# LM3488_Sheet1.net
KiCad netlist of a schematic drawn in Altium Designer
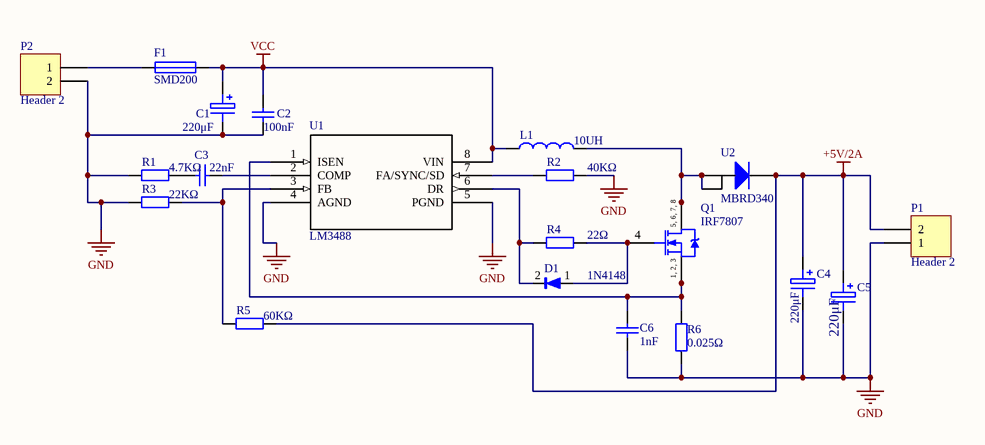
[diagram p0: LM3488_Sheet1.SchDoc]

(export (version "E")
  (design (tool "Eeschema 10.0.6"))
  (components
    (comp (ref "C1")
      (value "220μF")
      (footprint "RB-220T")
      (description "Electrolytic Capacitor")
      (libsource (lib "myIntegrated_Library1") (part "CAP ELECTRO1"))
    )
    (comp (ref "C2")
      (value "100nF")
      (footprint "0805")
      (description "Capacitor")
      (fields (field (name "Comment") "Cap") (field (name "PUBLISHER") "Altium Limited"))
      (libsource (lib "Miscellaneous Devices") (part "Cap"))
    )
    (comp (ref "C3")
      (value "22nF")
      (footprint "0805")
      (description "Capacitor")
      (fields (field (name "Comment") "Cap") (field (name "PUBLISHER") "Altium Limited"))
      (libsource (lib "Miscellaneous Devices") (part "Cap"))
    )
    (comp (ref "C4")
      (value "220μF,16V,Ф6.3×7.7mm")
      (footprint "RB-220T")
      (description "Electrolytic Capacitor")
      (fields (field (name "规格型号") "220μF"))
      (libsource (lib "myIntegrated_Library1") (part "CAP ELECTRO1"))
    )
    (comp (ref "C5")
      (value "220μF,16V,Ф6.3×7.7mm")
      (footprint "RB-220T")
      (description "Electrolytic Capacitor")
      (fields (field (name "规格型号") "220μF"))
      (libsource (lib "myIntegrated_Library1") (part "CAP ELECTRO1"))
    )
    (comp (ref "C6")
      (value "1nF")
      (footprint "0805")
      (description "Capacitor")
      (fields (field (name "Comment") "Cap") (field (name "PUBLISHER") "Altium Limited"))
      (libsource (lib "Miscellaneous Devices") (part "Cap"))
    )
    (comp (ref "D1")
      (value "1N4148")
      (footprint "SOD-1005A")
      (description "单向导通二极管")
      (fields (field (name "Comment") "DIODE1"))
      (libsource (lib "myIntegrated_Library1") (part "DIODE1_1"))
    )
    (comp (ref "F1")
      (value "SMD200")
      (footprint "1812")
      (description "Fuse")
      (libsource (lib "myIntegrated_Library1") (part "FUSE1"))
    )
    (comp (ref "L1")
      (value "10UH")
      (footprint "L-12X12S")
      (fields (field (name "Comment") "INDUCTOR1"))
      (libsource (lib "myIntegrated_Library1") (part "INDUCTOR1"))
    )
    (comp (ref "P1")
      (value "Header 2")
      (footprint "8.5端子")
      (description "Header, 2-Pin")
      (fields (field (name "PUBLISHER") "Altium Limited"))
      (libsource (lib "") (part "Header 2_1"))
    )
    (comp (ref "P2")
      (value "Header 2")
      (footprint "8.5端子")
      (description "Header, 2-Pin")
      (fields (field (name "PUBLISHER") "Altium Limited"))
      (libsource (lib "Miscellaneous Connectors") (part "Header 2"))
    )
    (comp (ref "Q1")
      (value "IRF7807")
      (footprint "SO-8_N")
      (description "HEXFET Power MOSFET")
      (fields (field (name "PUBLISHER") "Altium Limited"))
      (libsource (lib "IR Discrete MOSFET - Power") (part "IRF7807"))
    )
    (comp (ref "R1")
      (value "4.7KΩ")
      (footprint "0805_R")
      (description "贴片电阻")
      (libsource (lib "Miscellaneous Devices LC") (part "0805 1.5KΩ (1501) 1%"))
    )
    (comp (ref "R2")
      (value "40KΩ")
      (footprint "0805_R")
      (description "贴片电阻")
      (libsource (lib "Miscellaneous Devices LC") (part "0805 1.5KΩ (1501) 1%"))
    )
    (comp (ref "R3")
      (value "22KΩ")
      (footprint "0805_R")
      (description "贴片电阻")
      (libsource (lib "Miscellaneous Devices LC") (part "0805 1.5KΩ (1501) 1%"))
    )
    (comp (ref "R4")
      (value "22Ω")
      (footprint "0805_R")
      (description "贴片电阻")
      (libsource (lib "Miscellaneous Devices LC") (part "0805 1.5KΩ (1501) 1%"))
    )
    (comp (ref "R5")
      (value "60KΩ")
      (footprint "0805_R")
      (description "贴片电阻")
      (libsource (lib "Miscellaneous Devices LC") (part "0805 1.5KΩ (1501) 1%"))
    )
    (comp (ref "R6")
      (value "0.025Ω")
      (footprint "0805_R")
      (description "贴片电阻")
      (libsource (lib "") (part "0805 1.5KΩ (1501) 1%_1"))
    )
    (comp (ref "U1")
      (value "LM3488")
      (footprint "LM3488")
      (libsource (lib "myIntegrated_Library1") (part "LM3488"))
    )
    (comp (ref "U2")
      (value "MBRD340")
      (footprint "TO252")
      (description "大功率二极管")
      (libsource (lib "myIntegrated_Library1") (part "MBRD340"))
    )
  )
  (nets
    (net (code "1") (name "+5V{slash}2A") (class "Default")
      (node (ref "C4") (pin "1") (pinfunction "1_1") (pintype "passive"))
      (node (ref "C5") (pin "1") (pinfunction "1_1") (pintype "passive"))
      (node (ref "P1") (pin "2") (pinfunction "2_2") (pintype "passive"))
      (node (ref "R5") (pin "2") (pinfunction "2_2") (pintype "passive"))
      (node (ref "U2") (pin "4") (pinfunction "4_4") (pintype "passive"))
    )
    (net (code "2") (name "GND") (class "Default")
      (node (ref "C1") (pin "2") (pinfunction "2_2") (pintype "passive"))
      (node (ref "C2") (pin "2") (pinfunction "2_2") (pintype "passive"))
      (node (ref "C4") (pin "2") (pinfunction "2_2") (pintype "passive"))
      (node (ref "C5") (pin "2") (pinfunction "2_2") (pintype "passive"))
      (node (ref "C6") (pin "2") (pinfunction "2_2") (pintype "passive"))
      (node (ref "P1") (pin "1") (pinfunction "1_1") (pintype "passive"))
      (node (ref "P2") (pin "2") (pinfunction "2_2") (pintype "passive"))
      (node (ref "R1") (pin "1") (pinfunction "1_1") (pintype "passive"))
      (node (ref "R2") (pin "2") (pinfunction "2_2") (pintype "passive"))
      (node (ref "R3") (pin "1") (pinfunction "1_1") (pintype "passive"))
      (node (ref "R6") (pin "1") (pinfunction "1_1") (pintype "passive"))
      (node (ref "U1") (pin "4") (pinfunction "AGND_4") (pintype "power_in"))
      (node (ref "U1") (pin "5") (pinfunction "PGND_5") (pintype "power_in"))
    )
    (net (code "3") (name "Net-(C3-Pad2)") (class "Default")
      (node (ref "C3") (pin "2") (pinfunction "2_2") (pintype "passive"))
      (node (ref "R1") (pin "2") (pinfunction "2_2") (pintype "passive"))
    )
    (net (code "4") (name "Net-(F1-Pad1)") (class "Default")
      (node (ref "F1") (pin "1") (pinfunction "1_1") (pintype "passive"))
      (node (ref "P2") (pin "1") (pinfunction "1_1") (pintype "passive"))
    )
    (net (code "5") (name "Net-(L1-Pad2)") (class "Default")
      (node (ref "L1") (pin "2") (pinfunction "2_2") (pintype "passive"))
      (node (ref "Q1") (pin "5") (pinfunction "D_5") (pintype "passive"))
      (node (ref "Q1") (pin "6") (pinfunction "D_6") (pintype "passive"))
      (node (ref "Q1") (pin "7") (pinfunction "D_7") (pintype "passive"))
      (node (ref "Q1") (pin "8") (pinfunction "D_8") (pintype "passive"))
      (node (ref "U2") (pin "1") (pinfunction "1_1") (pintype "passive"))
      (node (ref "U2") (pin "3") (pinfunction "3_3") (pintype "passive"))
    )
    (net (code "6") (name "Net-(Q1-G)") (class "Default")
      (node (ref "D1") (pin "1") (pinfunction "1_1") (pintype "passive"))
      (node (ref "Q1") (pin "4") (pinfunction "G_4") (pintype "passive"))
      (node (ref "R4") (pin "2") (pinfunction "2_2") (pintype "passive"))
    )
    (net (code "7") (name "Net-(U1-COMP)") (class "Default")
      (node (ref "C3") (pin "1") (pinfunction "1_1") (pintype "passive"))
      (node (ref "U1") (pin "2") (pinfunction "COMP_2") (pintype "passive"))
    )
    (net (code "8") (name "Net-(U1-DR)") (class "Default")
      (node (ref "D1") (pin "2") (pinfunction "2_2") (pintype "passive"))
      (node (ref "R4") (pin "1") (pinfunction "1_1") (pintype "passive"))
      (node (ref "U1") (pin "6") (pinfunction "DR_6") (pintype "output"))
    )
    (net (code "9") (name "Net-(U1-FA{slash}SYNC{slash}SD)") (class "Default")
      (node (ref "R2") (pin "1") (pinfunction "1_1") (pintype "passive"))
      (node (ref "U1") (pin "7") (pinfunction "FA/SYNC/SD_7") (pintype "input"))
    )
    (net (code "10") (name "Net-(U1-FB)") (class "Default")
      (node (ref "R3") (pin "2") (pinfunction "2_2") (pintype "passive"))
      (node (ref "R5") (pin "1") (pinfunction "1_1") (pintype "passive"))
      (node (ref "U1") (pin "3") (pinfunction "FB_3") (pintype "input"))
    )
    (net (code "11") (name "Net-(U1-ISEN)") (class "Default")
      (node (ref "C6") (pin "1") (pinfunction "1_1") (pintype "passive"))
      (node (ref "Q1") (pin "1") (pinfunction "S_1") (pintype "passive"))
      (node (ref "Q1") (pin "2") (pinfunction "S_2") (pintype "passive"))
      (node (ref "Q1") (pin "3") (pinfunction "S_3") (pintype "passive"))
      (node (ref "R6") (pin "2") (pinfunction "2_2") (pintype "passive"))
      (node (ref "U1") (pin "1") (pinfunction "ISEN_1") (pintype "input"))
    )
    (net (code "12") (name "VCC") (class "Default")
      (node (ref "C1") (pin "1") (pinfunction "1_1") (pintype "passive"))
      (node (ref "C2") (pin "1") (pinfunction "1_1") (pintype "passive"))
      (node (ref "F1") (pin "2") (pinfunction "2_2") (pintype "passive"))
      (node (ref "L1") (pin "1") (pinfunction "1_1") (pintype "passive"))
      (node (ref "U1") (pin "8") (pinfunction "VIN_8") (pintype "power_in"))
    )
  )
)
